# DC-DC-converter_v2.net
KiCad netlist of a schematic drawn in Altium Designer
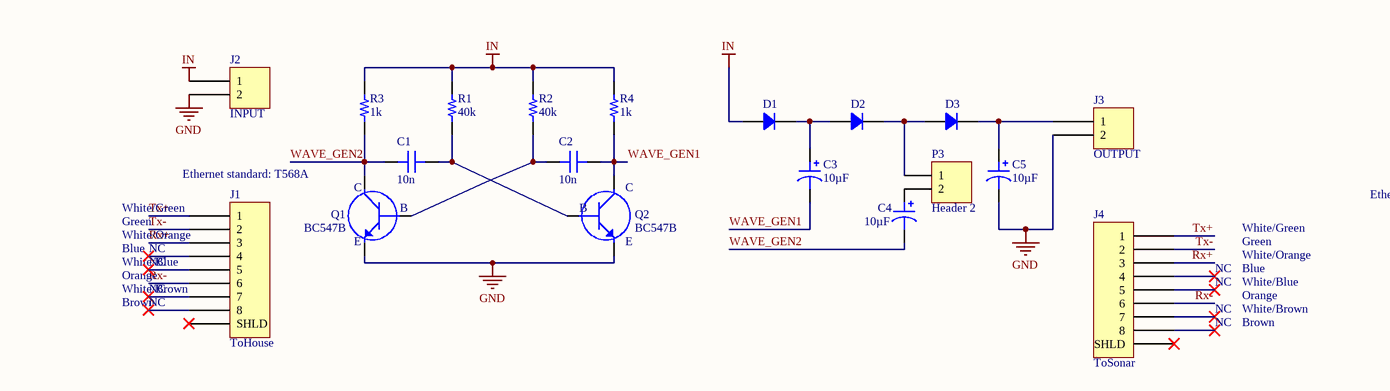
[diagram p0: DC-DC-converter_v2.SchDoc]

(export (version "E")
  (design (tool "Eeschema 10.0.6"))
  (components
    (comp (ref "C1")
      (value "10n")
      (footprint "CAP 0805_2012")
      (description "CAP CER 33PF 250V C0G/NP0 0805")
      (fields (field (name "PART NUMBER") "CBR08C330JAGAC"))
      (libsource (lib "Celestial Altium Library - altium_library") (part "Capacitor"))
    )
    (comp (ref "C2")
      (value "10n")
      (footprint "CAP 0805_2012")
      (description "CAP CER 33PF 250V C0G/NP0 0805")
      (fields (field (name "PART NUMBER") "CBR08C330JAGAC"))
      (libsource (lib "Celestial Altium Library - altium_library") (part "Capacitor"))
    )
    (comp (ref "C3")
      (value "10µF")
      (footprint "CAP ALSMD 6.6MM H6.1MM")
      (description "CAP ALUM 10UF 20% 63V SMD")
      (fields (field (name "PART NUMBER") "EDK106M063A9GAA") (field (name "MANUFACTURER") "KEMET"))
      (libsource (lib "Celestial Altium Library - altium_library") (part "Polarised Capacitor"))
    )
    (comp (ref "C4")
      (value "10µF")
      (footprint "CAP ALSMD 6.6MM H6.1MM")
      (description "CAP ALUM 10UF 20% 63V SMD")
      (fields (field (name "PART NUMBER") "EDK106M063A9GAA") (field (name "MANUFACTURER") "KEMET"))
      (libsource (lib "Celestial Altium Library - altium_library") (part "Polarised Capacitor"))
    )
    (comp (ref "C5")
      (value "10µF")
      (footprint "CAP ALSMD 6.6MM H6.1MM")
      (description "CAP ALUM 10UF 20% 63V SMD")
      (fields (field (name "PART NUMBER") "EDK106M063A9GAA") (field (name "MANUFACTURER") "KEMET"))
      (libsource (lib "Celestial Altium Library - altium_library") (part "Polarised Capacitor"))
    )
    (comp (ref "D1")
      (value "MBR0580-TP")
      (footprint "SOD-123")
      (description "DIODE SCHOTTKY 80V 500MA SOD123")
      (fields (field (name "MANUFACTURER") "Micro Commercial Co"))
      (libsource (lib "Celestial Altium Library - altium_library") (part "Diode"))
    )
    (comp (ref "D2")
      (value "MBR0580-TP")
      (footprint "SOD-123")
      (description "DIODE SCHOTTKY 80V 500MA SOD123")
      (fields (field (name "MANUFACTURER") "Micro Commercial Co"))
      (libsource (lib "Celestial Altium Library - altium_library") (part "Diode"))
    )
    (comp (ref "D3")
      (value "MBR0580-TP")
      (footprint "SOD-123")
      (description "DIODE SCHOTTKY 80V 500MA SOD123")
      (fields (field (name "MANUFACTURER") "Micro Commercial Co"))
      (libsource (lib "Celestial Altium Library - altium_library") (part "Diode"))
    )
    (comp (ref "J1")
      (value "A-2004-2-4-LPS-N-R")
      (footprint "ASSMANN A-2004-2-4-LPS-N-R")
      (description "CONN MOD JACK 8P8C R/A SHIELDED")
      (fields
        (field (name "MANUFACTURER") "Assmann WSW Components")
        (field (name "CUSTOM DESCRIPTION 2") "ToHouse")
      )
      (libsource (lib "Celestial Altium Library - altium_library") (part "Modular Jack with Shield"))
    )
    (comp (ref "J2")
      (value "0022272021")
      (footprint "MOLEX KK 0022272021")
      (description "CONN HEADER VERT 2POS 2.54MM")
      (fields (field (name "MANUFACTURER") "Molex") (field (name "CUSTOM DESCRIPTION") "INPUT"))
      (libsource (lib "Celestial Altium Library - altium_library") (part "2 Pin"))
    )
    (comp (ref "J3")
      (value "0022272021")
      (footprint "MOLEX KK 0022272021")
      (description "CONN HEADER VERT 2POS 2.54MM")
      (fields (field (name "MANUFACTURER") "Molex") (field (name "CUSTOM DESCRIPTION") "OUTPUT"))
      (libsource (lib "Celestial Altium Library - altium_library") (part "2 Pin"))
    )
    (comp (ref "J4")
      (value "A-2004-2-4-LPS-N-R")
      (footprint "ASSMANN A-2004-2-4-LPS-N-R")
      (description "CONN MOD JACK 8P8C R/A SHIELDED")
      (fields
        (field (name "MANUFACTURER") "Assmann WSW Components")
        (field (name "CUSTOM DESCRIPTION 2") "ToSonar")
      )
      (libsource (lib "") (part "Modular Jack with Shield_1"))
    )
    (comp (ref "P3")
      (value "Header 2")
      (footprint "HDR1X2")
      (description "Header, 2-Pin")
      (fields (field (name "PUBLISHER") "Altium Limited"))
      (libsource (lib "Miscellaneous Connectors") (part "Header 2"))
    )
    (comp (ref "Q1") (value "BC547B") (footprint "BC547B") (libsource (lib "BC547B") (part "BC547B")))
    (comp (ref "Q2") (value "BC547B") (footprint "BC547B") (libsource (lib "BC547B") (part "BC547B")))
    (comp (ref "R1")
      (value "40k")
      (footprint "RES 0805_2012")
      (description "RES 0 OHM JUMPER 0805")
      (fields (field (name "PART NUMBER") "TLRZ2ATTD"))
      (libsource (lib "Celestial Altium Library - altium_library") (part "Resistor"))
    )
    (comp (ref "R2")
      (value "40k")
      (footprint "RES 0805_2012")
      (description "RES 0 OHM JUMPER 0805")
      (fields (field (name "PART NUMBER") "TLRZ2ATTD"))
      (libsource (lib "Celestial Altium Library - altium_library") (part "Resistor"))
    )
    (comp (ref "R3")
      (value "1k")
      (footprint "RES 0805_2012")
      (description "RES 0 OHM JUMPER 0805")
      (fields (field (name "PART NUMBER") "TLRZ2ATTD"))
      (libsource (lib "Celestial Altium Library - altium_library") (part "Resistor"))
    )
    (comp (ref "R4")
      (value "1k")
      (footprint "RES 0805_2012")
      (description "RES 0 OHM JUMPER 0805")
      (fields (field (name "PART NUMBER") "TLRZ2ATTD"))
      (libsource (lib "Celestial Altium Library - altium_library") (part "Resistor"))
    )
  )
  (nets
    (net (code "1") (name "/Rx+") (class "Default")
      (node (ref "J1") (pin "3") (pinfunction "3_3") (pintype "passive"))
      (node (ref "J4") (pin "3") (pinfunction "3_3") (pintype "passive"))
    )
    (net (code "2") (name "/Rx-") (class "Default")
      (node (ref "J1") (pin "6") (pinfunction "6_6") (pintype "passive"))
      (node (ref "J4") (pin "6") (pinfunction "6_6") (pintype "passive"))
    )
    (net (code "3") (name "/Tx+") (class "Default")
      (node (ref "J1") (pin "1") (pinfunction "1_1") (pintype "passive"))
      (node (ref "J4") (pin "1") (pinfunction "1_1") (pintype "passive"))
    )
    (net (code "4") (name "/Tx-") (class "Default")
      (node (ref "J1") (pin "2") (pinfunction "2_2") (pintype "passive"))
      (node (ref "J4") (pin "2") (pinfunction "2_2") (pintype "passive"))
    )
    (net (code "5") (name "/WAVE_GEN1") (class "Default")
      (node (ref "C2") (pin "2") (pinfunction "2_2") (pintype "passive"))
      (node (ref "C3") (pin "2") (pinfunction "2_2") (pintype "passive"))
      (node (ref "Q2") (pin "1") (pinfunction "1_1") (pintype "passive"))
      (node (ref "R4") (pin "2") (pinfunction "2_2") (pintype "passive"))
    )
    (net (code "6") (name "/WAVE_GEN2") (class "Default")
      (node (ref "C1") (pin "1") (pinfunction "1_1") (pintype "passive"))
      (node (ref "C4") (pin "2") (pinfunction "2_2") (pintype "passive"))
      (node (ref "Q1") (pin "1") (pinfunction "1_1") (pintype "passive"))
      (node (ref "R3") (pin "2") (pinfunction "2_2") (pintype "passive"))
    )
    (net (code "7") (name "GND") (class "Default")
      (node (ref "C5") (pin "2") (pinfunction "2_2") (pintype "passive"))
      (node (ref "J2") (pin "2") (pinfunction "2_2") (pintype "passive"))
      (node (ref "J3") (pin "2") (pinfunction "2_2") (pintype "passive"))
      (node (ref "Q1") (pin "3") (pinfunction "3_3") (pintype "passive"))
      (node (ref "Q2") (pin "3") (pinfunction "3_3") (pintype "passive"))
    )
    (net (code "8") (name "IN") (class "Default")
      (node (ref "D1") (pin "1") (pinfunction "1_1") (pintype "passive"))
      (node (ref "J2") (pin "1") (pinfunction "1_1") (pintype "passive"))
      (node (ref "R1") (pin "1") (pinfunction "1_1") (pintype "passive"))
      (node (ref "R2") (pin "2") (pinfunction "2_2") (pintype "passive"))
      (node (ref "R3") (pin "1") (pinfunction "1_1") (pintype "passive"))
      (node (ref "R4") (pin "1") (pinfunction "1_1") (pintype "passive"))
    )
    (net (code "9") (name "Net-(C1-Pad2)") (class "Default")
      (node (ref "C1") (pin "2") (pinfunction "2_2") (pintype "passive"))
      (node (ref "Q2") (pin "2") (pinfunction "2_2") (pintype "passive"))
      (node (ref "R1") (pin "2") (pinfunction "2_2") (pintype "passive"))
    )
    (net (code "10") (name "Net-(C2-Pad1)") (class "Default")
      (node (ref "C2") (pin "1") (pinfunction "1_1") (pintype "passive"))
      (node (ref "Q1") (pin "2") (pinfunction "2_2") (pintype "passive"))
      (node (ref "R2") (pin "1") (pinfunction "1_1") (pintype "passive"))
    )
    (net (code "11") (name "Net-(C3-Pad1)") (class "Default")
      (node (ref "C3") (pin "1") (pinfunction "1_1") (pintype "passive"))
      (node (ref "D1") (pin "2") (pinfunction "2_2") (pintype "passive"))
      (node (ref "D2") (pin "1") (pinfunction "1_1") (pintype "passive"))
    )
    (net (code "12") (name "Net-(C4-Pad1)") (class "Default")
      (node (ref "C4") (pin "1") (pinfunction "1_1") (pintype "passive"))
      (node (ref "P3") (pin "2") (pinfunction "2_2") (pintype "passive"))
    )
    (net (code "13") (name "Net-(C5-Pad1)") (class "Default")
      (node (ref "C5") (pin "1") (pinfunction "1_1") (pintype "passive"))
      (node (ref "D3") (pin "2") (pinfunction "2_2") (pintype "passive"))
      (node (ref "J3") (pin "1") (pinfunction "1_1") (pintype "passive"))
    )
    (net (code "14") (name "Net-(D2-Pad2)") (class "Default")
      (node (ref "D2") (pin "2") (pinfunction "2_2") (pintype "passive"))
      (node (ref "D3") (pin "1") (pinfunction "1_1") (pintype "passive"))
      (node (ref "P3") (pin "1") (pinfunction "1_1") (pintype "passive"))
    )
    (net (code "15") (name "unconnected-(J1-Pad4)") (class "Default")
      (node (ref "J1") (pin "4") (pinfunction "4_4") (pintype "passive+no_connect"))
    )
    (net (code "16") (name "unconnected-(J1-Pad5)") (class "Default")
      (node (ref "J1") (pin "5") (pinfunction "5_5") (pintype "passive+no_connect"))
    )
    (net (code "17") (name "unconnected-(J1-Pad7)") (class "Default")
      (node (ref "J1") (pin "7") (pinfunction "7_7") (pintype "passive+no_connect"))
    )
    (net (code "18") (name "unconnected-(J1-Pad8)") (class "Default")
      (node (ref "J1") (pin "8") (pinfunction "8_8") (pintype "passive+no_connect"))
    )
    (net (code "19") (name "unconnected-(J1-SHLD-PadS)") (class "Default")
      (node (ref "J1") (pin "S") (pinfunction "SHLD_S") (pintype "passive+no_connect"))
    )
    (net (code "20") (name "unconnected-(J4-Pad4)") (class "Default")
      (node (ref "J4") (pin "4") (pinfunction "4_4") (pintype "passive+no_connect"))
    )
    (net (code "21") (name "unconnected-(J4-Pad5)") (class "Default")
      (node (ref "J4") (pin "5") (pinfunction "5_5") (pintype "passive+no_connect"))
    )
    (net (code "22") (name "unconnected-(J4-Pad7)") (class "Default")
      (node (ref "J4") (pin "7") (pinfunction "7_7") (pintype "passive+no_connect"))
    )
    (net (code "23") (name "unconnected-(J4-Pad8)") (class "Default")
      (node (ref "J4") (pin "8") (pinfunction "8_8") (pintype "passive+no_connect"))
    )
    (net (code "24") (name "unconnected-(J4-SHLD-PadS)") (class "Default")
      (node (ref "J4") (pin "S") (pinfunction "SHLD_S") (pintype "passive+no_connect"))
    )
  )
)
